# DDS_Function_Generator.net
KiCad netlist of a schematic drawn in EAGLE
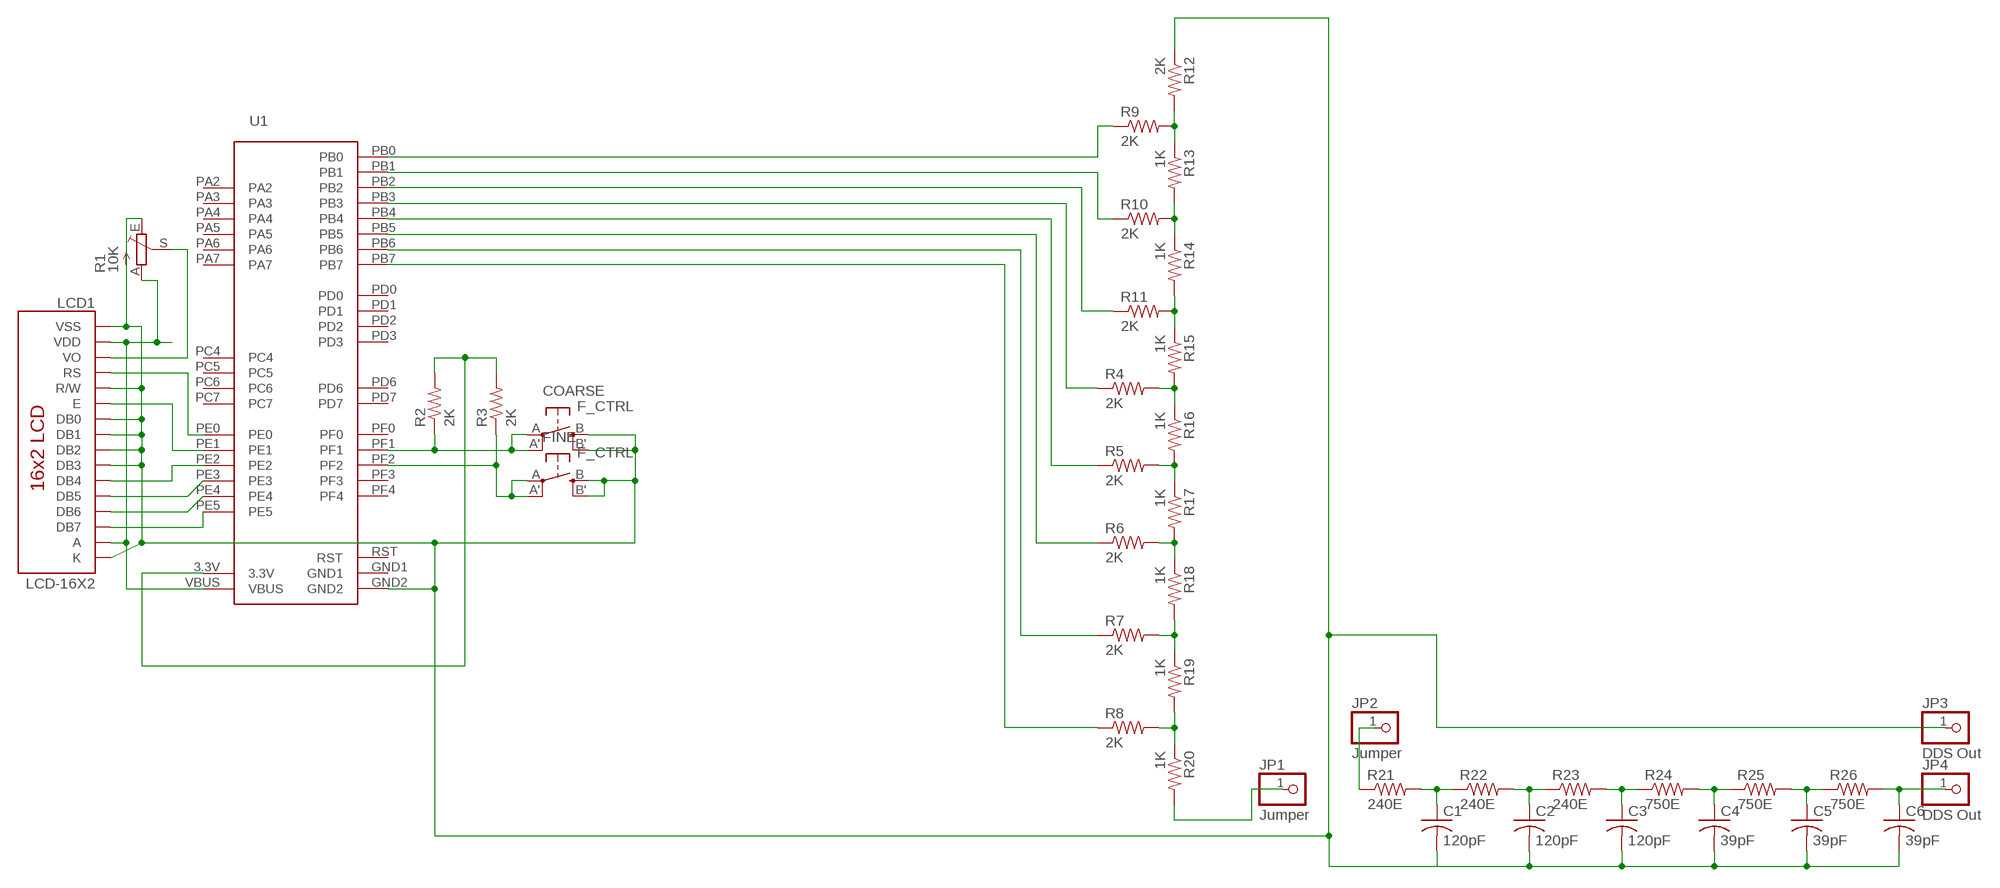
[diagram p0: schematic, sheet 1]

(export (version "E")
  (design (tool "Eeschema 10.0.6"))
  (components
    (comp (ref "C1")
      (value "120pF")
      (footprint "eagle-import:C0805")
      (libsource (lib "eagle-import") (part "C-USC0805"))
    )
    (comp (ref "C2")
      (value "120pF")
      (footprint "eagle-import:C0805")
      (libsource (lib "eagle-import") (part "C-USC0805"))
    )
    (comp (ref "C3")
      (value "120pF")
      (footprint "eagle-import:C0805")
      (libsource (lib "eagle-import") (part "C-USC0805"))
    )
    (comp (ref "C4")
      (value "39pF")
      (footprint "eagle-import:C0603")
      (libsource (lib "eagle-import") (part "C-USC0603"))
    )
    (comp (ref "C5")
      (value "39pF")
      (footprint "eagle-import:C0603")
      (libsource (lib "eagle-import") (part "C-USC0603"))
    )
    (comp (ref "C6")
      (value "39pF")
      (footprint "eagle-import:C0603")
      (libsource (lib "eagle-import") (part "C-USC0603"))
    )
    (comp (ref "COARSE")
      (value "F_CTRL")
      (footprint "eagle-import:EVQ-Q2")
      (libsource (lib "eagle-import") (part "SPST_TACT-EVQQ2"))
    )
    (comp (ref "FINE")
      (value "F_CTRL")
      (footprint "eagle-import:EVQ-Q2")
      (libsource (lib "eagle-import") (part "SPST_TACT-EVQQ2"))
    )
    (comp (ref "JP1")
      (value "Jumper")
      (footprint "eagle-import:1X01")
      (libsource (lib "eagle-import") (part "PINHD-1X1"))
    )
    (comp (ref "JP2")
      (value "Jumper")
      (footprint "eagle-import:1X01")
      (libsource (lib "eagle-import") (part "PINHD-1X1"))
    )
    (comp (ref "JP3")
      (value "DDS Out")
      (footprint "eagle-import:1X01")
      (libsource (lib "eagle-import") (part "PINHD-1X1"))
    )
    (comp (ref "JP4")
      (value "DDS Out")
      (footprint "eagle-import:1X01")
      (libsource (lib "eagle-import") (part "PINHD-1X1"))
    )
    (comp (ref "LCD1")
      (value "LCD-16X2")
      (footprint "eagle-import:LCD-16X2_NOHOLESNOSILK")
      (libsource (lib "eagle-import") (part "LCD-16X2NOHOLES"))
    )
    (comp (ref "R1")
      (value "10K")
      (footprint "eagle-import:B25P")
      (libsource (lib "eagle-import") (part "TRIM_EU-B25P"))
    )
    (comp (ref "R2")
      (value "2K")
      (footprint "eagle-import:R1206")
      (libsource (lib "eagle-import") (part "R-US_R1206"))
    )
    (comp (ref "R3")
      (value "2K")
      (footprint "eagle-import:R1206")
      (libsource (lib "eagle-import") (part "R-US_R1206"))
    )
    (comp (ref "R4")
      (value "2K")
      (footprint "eagle-import:R1206")
      (libsource (lib "eagle-import") (part "R-US_R1206"))
    )
    (comp (ref "R5")
      (value "2K")
      (footprint "eagle-import:R1206")
      (libsource (lib "eagle-import") (part "R-US_R1206"))
    )
    (comp (ref "R6")
      (value "2K")
      (footprint "eagle-import:R1206")
      (libsource (lib "eagle-import") (part "R-US_R1206"))
    )
    (comp (ref "R7")
      (value "2K")
      (footprint "eagle-import:R1206")
      (libsource (lib "eagle-import") (part "R-US_R1206"))
    )
    (comp (ref "R8")
      (value "2K")
      (footprint "eagle-import:R1206")
      (libsource (lib "eagle-import") (part "R-US_R1206"))
    )
    (comp (ref "R9")
      (value "2K")
      (footprint "eagle-import:R1206")
      (libsource (lib "eagle-import") (part "R-US_R1206"))
    )
    (comp (ref "R10")
      (value "2K")
      (footprint "eagle-import:R1206")
      (libsource (lib "eagle-import") (part "R-US_R1206"))
    )
    (comp (ref "R11")
      (value "2K")
      (footprint "eagle-import:R1206")
      (libsource (lib "eagle-import") (part "R-US_R1206"))
    )
    (comp (ref "R12")
      (value "2K")
      (footprint "eagle-import:R1206")
      (libsource (lib "eagle-import") (part "R-US_R1206"))
    )
    (comp (ref "R13")
      (value "1K")
      (footprint "eagle-import:R1206")
      (libsource (lib "eagle-import") (part "R-US_R1206"))
    )
    (comp (ref "R14")
      (value "1K")
      (footprint "eagle-import:R1206")
      (libsource (lib "eagle-import") (part "R-US_R1206"))
    )
    (comp (ref "R15")
      (value "1K")
      (footprint "eagle-import:R1206")
      (libsource (lib "eagle-import") (part "R-US_R1206"))
    )
    (comp (ref "R16")
      (value "1K")
      (footprint "eagle-import:R1206")
      (libsource (lib "eagle-import") (part "R-US_R1206"))
    )
    (comp (ref "R17")
      (value "1K")
      (footprint "eagle-import:R1206")
      (libsource (lib "eagle-import") (part "R-US_R1206"))
    )
    (comp (ref "R18")
      (value "1K")
      (footprint "eagle-import:R1206")
      (libsource (lib "eagle-import") (part "R-US_R1206"))
    )
    (comp (ref "R19")
      (value "1K")
      (footprint "eagle-import:R1206")
      (libsource (lib "eagle-import") (part "R-US_R1206"))
    )
    (comp (ref "R20")
      (value "1K")
      (footprint "eagle-import:R1206")
      (libsource (lib "eagle-import") (part "R-US_R1206"))
    )
    (comp (ref "R21")
      (value "240E")
      (footprint "eagle-import:R1206")
      (libsource (lib "eagle-import") (part "R-US_R1206"))
    )
    (comp (ref "R22")
      (value "240E")
      (footprint "eagle-import:R1206")
      (libsource (lib "eagle-import") (part "R-US_R1206"))
    )
    (comp (ref "R23")
      (value "240E")
      (footprint "eagle-import:R1206")
      (libsource (lib "eagle-import") (part "R-US_R1206"))
    )
    (comp (ref "R24")
      (value "750E")
      (footprint "eagle-import:R1206")
      (libsource (lib "eagle-import") (part "R-US_R1206"))
    )
    (comp (ref "R25")
      (value "750E")
      (footprint "eagle-import:R1206")
      (libsource (lib "eagle-import") (part "R-US_R1206"))
    )
    (comp (ref "R26")
      (value "750E")
      (footprint "eagle-import:R1206")
      (libsource (lib "eagle-import") (part "R-US_R1206"))
    )
    (comp (ref "U1")
      (value "U1")
      (footprint "eagle-import:LAUNCHPAD-XL")
      (libsource (lib "eagle-import") (part "STELLARIS-LAUNCHPADSTELLARIS-LAUNCHPAD"))
    )
  )
  (nets
    (net (code "1") (name "/RST") (class "Default")
      (node (ref "U1") (pin "RST") (pinfunction "RST_RST") (pintype "power_in"))
    )
    (net (code "2") (name "Net-(C1-Pad1)") (class "Default")
      (node (ref "C1") (pin "1") (pinfunction "1_1") (pintype "passive"))
      (node (ref "R21") (pin "2") (pinfunction "2_2") (pintype "passive"))
      (node (ref "R22") (pin "1") (pinfunction "1_1") (pintype "passive"))
    )
    (net (code "3") (name "Net-(C2-Pad1)") (class "Default")
      (node (ref "C2") (pin "1") (pinfunction "1_1") (pintype "passive"))
      (node (ref "R22") (pin "2") (pinfunction "2_2") (pintype "passive"))
      (node (ref "R23") (pin "1") (pinfunction "1_1") (pintype "passive"))
    )
    (net (code "4") (name "Net-(C3-Pad1)") (class "Default")
      (node (ref "C3") (pin "1") (pinfunction "1_1") (pintype "passive"))
      (node (ref "R23") (pin "2") (pinfunction "2_2") (pintype "passive"))
      (node (ref "R24") (pin "1") (pinfunction "1_1") (pintype "passive"))
    )
    (net (code "5") (name "Net-(C4-Pad1)") (class "Default")
      (node (ref "C4") (pin "1") (pinfunction "1_1") (pintype "passive"))
      (node (ref "R24") (pin "2") (pinfunction "2_2") (pintype "passive"))
      (node (ref "R25") (pin "1") (pinfunction "1_1") (pintype "passive"))
    )
    (net (code "6") (name "Net-(C5-Pad1)") (class "Default")
      (node (ref "C5") (pin "1") (pinfunction "1_1") (pintype "passive"))
      (node (ref "R25") (pin "2") (pinfunction "2_2") (pintype "passive"))
      (node (ref "R26") (pin "1") (pinfunction "1_1") (pintype "passive"))
    )
    (net (code "7") (name "Net-(C6-Pad1)") (class "Default")
      (node (ref "C6") (pin "1") (pinfunction "1_1") (pintype "passive"))
      (node (ref "JP4") (pin "1") (pinfunction "1_1") (pintype "passive"))
      (node (ref "R26") (pin "2") (pinfunction "2_2") (pintype "passive"))
    )
    (net (code "8") (name "Net-(COARSE-P)") (class "Default")
      (node (ref "COARSE") (pin "A") (pinfunction "P_A") (pintype "passive"))
      (node (ref "COARSE") (pin "A'") (pinfunction "P1_A'") (pintype "passive"))
      (node (ref "R2") (pin "1") (pinfunction "1_1") (pintype "passive"))
      (node (ref "U1") (pin "PF1") (pinfunction "PF1_PF1") (pintype "bidirectional"))
    )
    (net (code "9") (name "Net-(COARSE-S)") (class "Default")
      (node (ref "C1") (pin "2") (pinfunction "2_2") (pintype "passive"))
      (node (ref "C2") (pin "2") (pinfunction "2_2") (pintype "passive"))
      (node (ref "C3") (pin "2") (pinfunction "2_2") (pintype "passive"))
      (node (ref "C4") (pin "2") (pinfunction "2_2") (pintype "passive"))
      (node (ref "C5") (pin "2") (pinfunction "2_2") (pintype "passive"))
      (node (ref "C6") (pin "2") (pinfunction "2_2") (pintype "passive"))
      (node (ref "COARSE") (pin "B") (pinfunction "S_B") (pintype "passive"))
      (node (ref "COARSE") (pin "B'") (pinfunction "S1_B'") (pintype "passive"))
      (node (ref "FINE") (pin "B") (pinfunction "S_B") (pintype "passive"))
      (node (ref "FINE") (pin "B'") (pinfunction "S1_B'") (pintype "passive"))
      (node (ref "JP3") (pin "1") (pinfunction "1_1") (pintype "passive"))
      (node (ref "LCD1") (pin "1") (pinfunction "VSS_1") (pintype "power_in"))
      (node (ref "LCD1") (pin "10") (pinfunction "DB3_10") (pintype "bidirectional"))
      (node (ref "LCD1") (pin "16") (pinfunction "K_16") (pintype "power_in"))
      (node (ref "LCD1") (pin "5") (pinfunction "R/W_5") (pintype "input"))
      (node (ref "LCD1") (pin "7") (pinfunction "DB0_7") (pintype "bidirectional"))
      (node (ref "LCD1") (pin "8") (pinfunction "DB1_8") (pintype "bidirectional"))
      (node (ref "LCD1") (pin "9") (pinfunction "DB2_9") (pintype "bidirectional"))
      (node (ref "R1") (pin "E") (pinfunction "E_E") (pintype "passive"))
      (node (ref "R12") (pin "1") (pinfunction "1_1") (pintype "passive"))
      (node (ref "U1") (pin "GND2") (pinfunction "GND2_GND2") (pintype "power_in"))
    )
    (net (code "10") (name "Net-(FINE-P)") (class "Default")
      (node (ref "FINE") (pin "A") (pinfunction "P_A") (pintype "passive"))
      (node (ref "FINE") (pin "A'") (pinfunction "P1_A'") (pintype "passive"))
      (node (ref "R3") (pin "1") (pinfunction "1_1") (pintype "passive"))
      (node (ref "U1") (pin "PF2") (pinfunction "PF2_PF2") (pintype "bidirectional"))
    )
    (net (code "11") (name "Net-(JP1-Pad1)") (class "Default")
      (node (ref "JP1") (pin "1") (pinfunction "1_1") (pintype "passive"))
      (node (ref "R20") (pin "2") (pinfunction "2_2") (pintype "passive"))
    )
    (net (code "12") (name "Net-(JP2-Pad1)") (class "Default")
      (node (ref "JP2") (pin "1") (pinfunction "1_1") (pintype "passive"))
      (node (ref "R21") (pin "1") (pinfunction "1_1") (pintype "passive"))
    )
    (net (code "13") (name "Net-(LCD1-A)") (class "Default")
      (node (ref "LCD1") (pin "15") (pinfunction "A_15") (pintype "power_in"))
      (node (ref "LCD1") (pin "2") (pinfunction "VDD_2") (pintype "power_in"))
      (node (ref "R1") (pin "A") (pinfunction "A_A") (pintype "passive"))
      (node (ref "U1") (pin "VBUS") (pinfunction "VBUS_VBUS") (pintype "power_in"))
    )
    (net (code "14") (name "Net-(LCD1-DB4)") (class "Default")
      (node (ref "LCD1") (pin "11") (pinfunction "DB4_11") (pintype "bidirectional"))
      (node (ref "U1") (pin "PE2") (pinfunction "PE2_PE2") (pintype "bidirectional"))
    )
    (net (code "15") (name "Net-(LCD1-DB5)") (class "Default")
      (node (ref "LCD1") (pin "12") (pinfunction "DB5_12") (pintype "bidirectional"))
      (node (ref "U1") (pin "PE3") (pinfunction "PE3_PE3") (pintype "bidirectional"))
    )
    (net (code "16") (name "Net-(LCD1-DB6)") (class "Default")
      (node (ref "LCD1") (pin "13") (pinfunction "DB6_13") (pintype "bidirectional"))
      (node (ref "U1") (pin "PE4") (pinfunction "PE4_PE4") (pintype "bidirectional"))
    )
    (net (code "17") (name "Net-(LCD1-DB7)") (class "Default")
      (node (ref "LCD1") (pin "14") (pinfunction "DB7_14") (pintype "bidirectional"))
      (node (ref "U1") (pin "PE5") (pinfunction "PE5_PE5") (pintype "bidirectional"))
    )
    (net (code "18") (name "Net-(LCD1-E)") (class "Default")
      (node (ref "LCD1") (pin "6") (pinfunction "E_6") (pintype "input"))
      (node (ref "U1") (pin "PE1") (pinfunction "PE1_PE1") (pintype "bidirectional"))
    )
    (net (code "19") (name "Net-(LCD1-RS)") (class "Default")
      (node (ref "LCD1") (pin "4") (pinfunction "RS_4") (pintype "input"))
      (node (ref "U1") (pin "PE0") (pinfunction "PE0_PE0") (pintype "bidirectional"))
    )
    (net (code "20") (name "Net-(LCD1-VO)") (class "Default")
      (node (ref "LCD1") (pin "3") (pinfunction "VO_3") (pintype "bidirectional"))
      (node (ref "R1") (pin "S") (pinfunction "S_S") (pintype "passive"))
    )
    (net (code "21") (name "Net-(R2-Pad2)") (class "Default")
      (node (ref "R2") (pin "2") (pinfunction "2_2") (pintype "passive"))
      (node (ref "R3") (pin "2") (pinfunction "2_2") (pintype "passive"))
      (node (ref "U1") (pin "3.3V") (pinfunction "3.3V_3.3V") (pintype "power_in"))
    )
    (net (code "22") (name "Net-(R4-Pad1)") (class "Default")
      (node (ref "R4") (pin "1") (pinfunction "1_1") (pintype "passive"))
      (node (ref "U1") (pin "PB3") (pinfunction "PB3_PB3") (pintype "bidirectional"))
    )
    (net (code "23") (name "Net-(R5-Pad1)") (class "Default")
      (node (ref "R5") (pin "1") (pinfunction "1_1") (pintype "passive"))
      (node (ref "U1") (pin "PB4") (pinfunction "PB4_PB4") (pintype "bidirectional"))
    )
    (net (code "24") (name "Net-(R6-Pad1)") (class "Default")
      (node (ref "R6") (pin "1") (pinfunction "1_1") (pintype "passive"))
      (node (ref "U1") (pin "PB5") (pinfunction "PB5_PB5") (pintype "bidirectional"))
    )
    (net (code "25") (name "Net-(R7-Pad1)") (class "Default")
      (node (ref "R7") (pin "1") (pinfunction "1_1") (pintype "passive"))
      (node (ref "U1") (pin "PB6") (pinfunction "PB6_PB6") (pintype "bidirectional"))
    )
    (net (code "26") (name "Net-(R8-Pad1)") (class "Default")
      (node (ref "R8") (pin "1") (pinfunction "1_1") (pintype "passive"))
      (node (ref "U1") (pin "PB7") (pinfunction "PB7_PB7") (pintype "bidirectional"))
    )
    (net (code "27") (name "Net-(R9-Pad1)") (class "Default")
      (node (ref "R9") (pin "1") (pinfunction "1_1") (pintype "passive"))
      (node (ref "U1") (pin "PB0") (pinfunction "PB0_PB0") (pintype "bidirectional"))
    )
    (net (code "28") (name "Net-(R10-Pad1)") (class "Default")
      (node (ref "R10") (pin "1") (pinfunction "1_1") (pintype "passive"))
      (node (ref "U1") (pin "PB1") (pinfunction "PB1_PB1") (pintype "bidirectional"))
    )
    (net (code "29") (name "Net-(R10-Pad2)") (class "Default")
      (node (ref "R10") (pin "2") (pinfunction "2_2") (pintype "passive"))
      (node (ref "R13") (pin "2") (pinfunction "2_2") (pintype "passive"))
      (node (ref "R14") (pin "1") (pinfunction "1_1") (pintype "passive"))
    )
    (net (code "30") (name "Net-(R11-Pad1)") (class "Default")
      (node (ref "R11") (pin "1") (pinfunction "1_1") (pintype "passive"))
      (node (ref "U1") (pin "PB2") (pinfunction "PB2_PB2") (pintype "bidirectional"))
    )
    (net (code "31") (name "Net-(R11-Pad2)") (class "Default")
      (node (ref "R11") (pin "2") (pinfunction "2_2") (pintype "passive"))
      (node (ref "R14") (pin "2") (pinfunction "2_2") (pintype "passive"))
      (node (ref "R15") (pin "1") (pinfunction "1_1") (pintype "passive"))
    )
    (net (code "32") (name "Net-(R12-Pad2)") (class "Default")
      (node (ref "R12") (pin "2") (pinfunction "2_2") (pintype "passive"))
      (node (ref "R13") (pin "1") (pinfunction "1_1") (pintype "passive"))
      (node (ref "R9") (pin "2") (pinfunction "2_2") (pintype "passive"))
    )
    (net (code "33") (name "Net-(R15-Pad2)") (class "Default")
      (node (ref "R15") (pin "2") (pinfunction "2_2") (pintype "passive"))
      (node (ref "R16") (pin "1") (pinfunction "1_1") (pintype "passive"))
      (node (ref "R4") (pin "2") (pinfunction "2_2") (pintype "passive"))
    )
    (net (code "34") (name "Net-(R16-Pad2)") (class "Default")
      (node (ref "R16") (pin "2") (pinfunction "2_2") (pintype "passive"))
      (node (ref "R17") (pin "1") (pinfunction "1_1") (pintype "passive"))
      (node (ref "R5") (pin "2") (pinfunction "2_2") (pintype "passive"))
    )
    (net (code "35") (name "Net-(R17-Pad2)") (class "Default")
      (node (ref "R17") (pin "2") (pinfunction "2_2") (pintype "passive"))
      (node (ref "R18") (pin "1") (pinfunction "1_1") (pintype "passive"))
      (node (ref "R6") (pin "2") (pinfunction "2_2") (pintype "passive"))
    )
    (net (code "36") (name "Net-(R18-Pad2)") (class "Default")
      (node (ref "R18") (pin "2") (pinfunction "2_2") (pintype "passive"))
      (node (ref "R19") (pin "1") (pinfunction "1_1") (pintype "passive"))
      (node (ref "R7") (pin "2") (pinfunction "2_2") (pintype "passive"))
    )
    (net (code "37") (name "Net-(R19-Pad2)") (class "Default")
      (node (ref "R19") (pin "2") (pinfunction "2_2") (pintype "passive"))
      (node (ref "R20") (pin "1") (pinfunction "1_1") (pintype "passive"))
      (node (ref "R8") (pin "2") (pinfunction "2_2") (pintype "passive"))
    )
    (net (code "38") (name "unconnected-(U1-PadGND1)") (class "Default")
      (node (ref "U1") (pin "GND1") (pinfunction "GND1_GND1") (pintype "bidirectional"))
    )
    (net (code "39") (name "unconnected-(U1-PadPA2)") (class "Default")
      (node (ref "U1") (pin "PA2") (pinfunction "PA2_PA2") (pintype "bidirectional"))
    )
    (net (code "40") (name "unconnected-(U1-PadPA3)") (class "Default")
      (node (ref "U1") (pin "PA3") (pinfunction "PA3_PA3") (pintype "bidirectional"))
    )
    (net (code "41") (name "unconnected-(U1-PadPA4)") (class "Default")
      (node (ref "U1") (pin "PA4") (pinfunction "PA4_PA4") (pintype "bidirectional"))
    )
    (net (code "42") (name "unconnected-(U1-PadPA5)") (class "Default")
      (node (ref "U1") (pin "PA5") (pinfunction "PA5_PA5") (pintype "bidirectional"))
    )
    (net (code "43") (name "unconnected-(U1-PadPA6)") (class "Default")
      (node (ref "U1") (pin "PA6") (pinfunction "PA6_PA6") (pintype "bidirectional"))
    )
    (net (code "44") (name "unconnected-(U1-PadPA7)") (class "Default")
      (node (ref "U1") (pin "PA7") (pinfunction "PA7_PA7") (pintype "bidirectional"))
    )
    (net (code "45") (name "unconnected-(U1-PadPC4)") (class "Default")
      (node (ref "U1") (pin "PC4") (pinfunction "PC4_PC4") (pintype "bidirectional"))
    )
    (net (code "46") (name "unconnected-(U1-PadPC5)") (class "Default")
      (node (ref "U1") (pin "PC5") (pinfunction "PC5_PC5") (pintype "bidirectional"))
    )
    (net (code "47") (name "unconnected-(U1-PadPC6)") (class "Default")
      (node (ref "U1") (pin "PC6") (pinfunction "PC6_PC6") (pintype "bidirectional"))
    )
    (net (code "48") (name "unconnected-(U1-PadPC7)") (class "Default")
      (node (ref "U1") (pin "PC7") (pinfunction "PC7_PC7") (pintype "bidirectional"))
    )
    (net (code "49") (name "unconnected-(U1-PadPD0)") (class "Default")
      (node (ref "U1") (pin "PD0") (pinfunction "PD0_PD0") (pintype "bidirectional"))
    )
    (net (code "50") (name "unconnected-(U1-PadPD1)") (class "Default")
      (node (ref "U1") (pin "PD1") (pinfunction "PD1_PD1") (pintype "bidirectional"))
    )
    (net (code "51") (name "unconnected-(U1-PadPD2)") (class "Default")
      (node (ref "U1") (pin "PD2") (pinfunction "PD2_PD2") (pintype "bidirectional"))
    )
    (net (code "52") (name "unconnected-(U1-PadPD3)") (class "Default")
      (node (ref "U1") (pin "PD3") (pinfunction "PD3_PD3") (pintype "bidirectional"))
    )
    (net (code "53") (name "unconnected-(U1-PadPD6)") (class "Default")
      (node (ref "U1") (pin "PD6") (pinfunction "PD6_PD6") (pintype "bidirectional"))
    )
    (net (code "54") (name "unconnected-(U1-PadPD7)") (class "Default")
      (node (ref "U1") (pin "PD7") (pinfunction "PD7_PD7") (pintype "bidirectional"))
    )
    (net (code "55") (name "unconnected-(U1-PadPF0)") (class "Default")
      (node (ref "U1") (pin "PF0") (pinfunction "PF0_PF0") (pintype "bidirectional"))
    )
    (net (code "56") (name "unconnected-(U1-PadPF3)") (class "Default")
      (node (ref "U1") (pin "PF3") (pinfunction "PF3_PF3") (pintype "bidirectional"))
    )
    (net (code "57") (name "unconnected-(U1-PadPF4)") (class "Default")
      (node (ref "U1") (pin "PF4") (pinfunction "PF4_PF4") (pintype "bidirectional"))
    )
  )
)
